# Pontos_Cegos_-_Rev_A.net
KiCad netlist of a schematic drawn in EAGLE
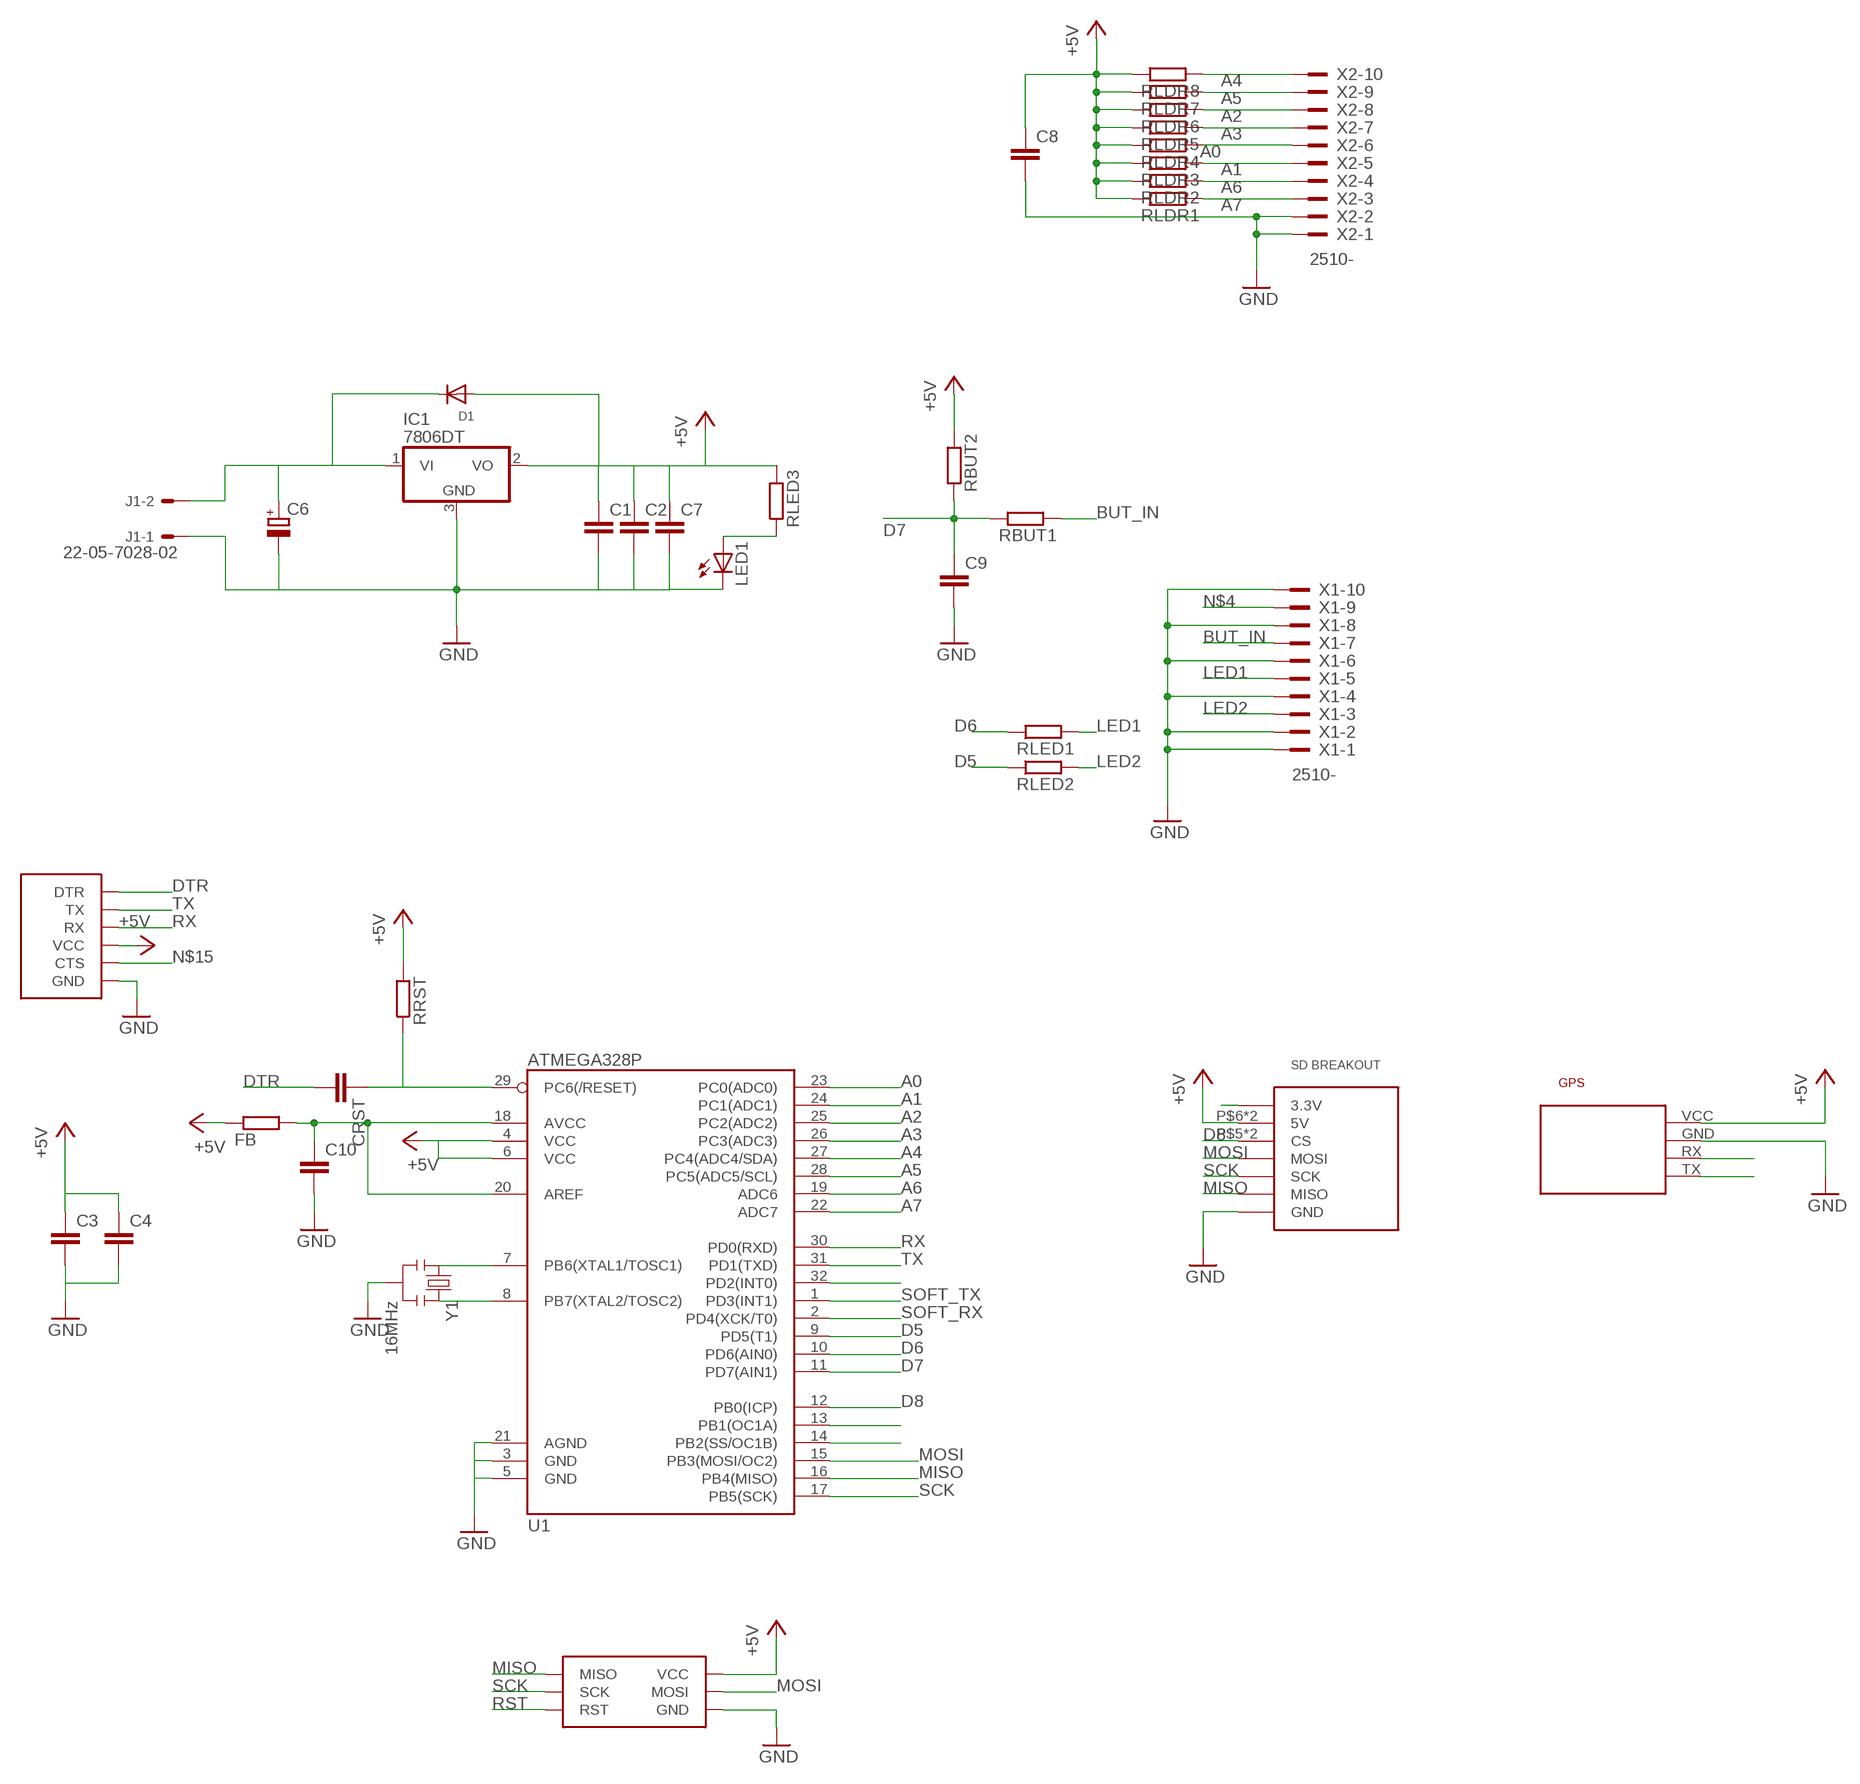
[diagram p0: schematic, sheet 1]

(export (version "E")
  (design (tool "Eeschema 10.0.6"))
  (components
    (comp (ref "C1")
      (value "C-EUC1210")
      (footprint "eagle-import:C1210")
      (libsource (lib "eagle-import") (part "C-EUC1210"))
    )
    (comp (ref "C2")
      (value "C-EUC1210")
      (footprint "eagle-import:C1210")
      (libsource (lib "eagle-import") (part "C-EUC1210"))
    )
    (comp (ref "C3")
      (value "C-EUC0603")
      (footprint "eagle-import:C0603")
      (libsource (lib "eagle-import") (part "C-EUC0603"))
    )
    (comp (ref "C4")
      (value "C-EUC0603")
      (footprint "eagle-import:C0603")
      (libsource (lib "eagle-import") (part "C-EUC0603"))
    )
    (comp (ref "C6")
      (value "CPOL-EUD")
      (footprint "eagle-import:PANASONIC_D")
      (libsource (lib "eagle-import") (part "CPOL-EUD"))
    )
    (comp (ref "C7")
      (value "C-EUC1210")
      (footprint "eagle-import:C1210")
      (libsource (lib "eagle-import") (part "C-EUC1210"))
    )
    (comp (ref "C8")
      (value "C-EUC0805")
      (footprint "eagle-import:C0805")
      (libsource (lib "eagle-import") (part "C-EUC0805"))
    )
    (comp (ref "C9")
      (value "C-EUC0805")
      (footprint "eagle-import:C0805")
      (libsource (lib "eagle-import") (part "C-EUC0805"))
    )
    (comp (ref "C10")
      (value "C-EUC0603")
      (footprint "eagle-import:C0603")
      (libsource (lib "eagle-import") (part "C-EUC0603"))
    )
    (comp (ref "CRST")
      (value "C-EUC0603")
      (footprint "eagle-import:C0603")
      (libsource (lib "eagle-import") (part "C-EUC0603"))
    )
    (comp (ref "D1")
      (value "DIODESMA")
      (footprint "eagle-import:SMADIODE")
      (libsource (lib "eagle-import") (part "DIODESMA"))
    )
    (comp (ref "FB")
      (value "R-EU_R0603")
      (footprint "eagle-import:R0603")
      (libsource (lib "eagle-import") (part "R-EU_R0603"))
    )
    (comp (ref "IC1")
      (value "7806DT")
      (footprint "eagle-import:TO252")
      (libsource (lib "eagle-import") (part "78DT06"))
    )
    (comp (ref "J1")
      (value "22-05-7028-02")
      (footprint "eagle-import:7395-02")
      (libsource (lib "eagle-import") (part "22-?-0205-7028"))
    )
    (comp (ref "LED1")
      (value "LED5MM")
      (footprint "eagle-import:LED5MM")
      (libsource (lib "eagle-import") (part "LED5MM"))
    )
    (comp (ref "RBUT1")
      (value "R-EU_R0603")
      (footprint "eagle-import:R0603")
      (libsource (lib "eagle-import") (part "R-EU_R0603"))
    )
    (comp (ref "RBUT2")
      (value "R-EU_R0603")
      (footprint "eagle-import:R0603")
      (libsource (lib "eagle-import") (part "R-EU_R0603"))
    )
    (comp (ref "RLDR1")
      (value "R-EU_R0603")
      (footprint "eagle-import:R0603")
      (libsource (lib "eagle-import") (part "R-EU_R0603"))
    )
    (comp (ref "RLDR2")
      (value "R-EU_R0603")
      (footprint "eagle-import:R0603")
      (libsource (lib "eagle-import") (part "R-EU_R0603"))
    )
    (comp (ref "RLDR3")
      (value "R-EU_R0603")
      (footprint "eagle-import:R0603")
      (libsource (lib "eagle-import") (part "R-EU_R0603"))
    )
    (comp (ref "RLDR4")
      (value "R-EU_R0603")
      (footprint "eagle-import:R0603")
      (libsource (lib "eagle-import") (part "R-EU_R0603"))
    )
    (comp (ref "RLDR5")
      (value "R-EU_R0603")
      (footprint "eagle-import:R0603")
      (libsource (lib "eagle-import") (part "R-EU_R0603"))
    )
    (comp (ref "RLDR6")
      (value "R-EU_R0603")
      (footprint "eagle-import:R0603")
      (libsource (lib "eagle-import") (part "R-EU_R0603"))
    )
    (comp (ref "RLDR7")
      (value "R-EU_R0603")
      (footprint "eagle-import:R0603")
      (libsource (lib "eagle-import") (part "R-EU_R0603"))
    )
    (comp (ref "RLDR8")
      (value "R-EU_R0603")
      (footprint "eagle-import:R0603")
      (libsource (lib "eagle-import") (part "R-EU_R0603"))
    )
    (comp (ref "RLED1")
      (value "R-EU_R0603")
      (footprint "eagle-import:R0603")
      (libsource (lib "eagle-import") (part "R-EU_R0603"))
    )
    (comp (ref "RLED2")
      (value "R-EU_R0603")
      (footprint "eagle-import:R0603")
      (libsource (lib "eagle-import") (part "R-EU_R0603"))
    )
    (comp (ref "RLED3")
      (value "R-EU_R0603")
      (footprint "eagle-import:R0603")
      (libsource (lib "eagle-import") (part "R-EU_R0603"))
    )
    (comp (ref "RRST")
      (value "R-EU_R0603")
      (footprint "eagle-import:R0603")
      (libsource (lib "eagle-import") (part "R-EU_R0603"))
    )
    (comp (ref "U$1")
      (value "ISP_POGOISP_POGO")
      (footprint "eagle-import:ISP_POGO")
      (libsource (lib "eagle-import") (part "ISP_POGOISP_POGO"))
    )
    (comp (ref "U$2")
      (value "SD_BREAKOUT")
      (footprint "eagle-import:SD_BREAKOUT")
      (libsource (lib "eagle-import") (part "SD_BREAKOUT"))
    )
    (comp (ref "U$3")
      (value "NEO6M_BREAKOUT")
      (footprint "eagle-import:NEO6M_BREAKOUT")
      (libsource (lib "eagle-import") (part "NEO6M_BREAKOUT"))
    )
    (comp (ref "U$4")
      (value "FTDI_HEADERSMD")
      (footprint "eagle-import:FTDI_HEADER_SMD")
      (libsource (lib "eagle-import") (part "FTDI_HEADERSMD"))
    )
    (comp (ref "U1")
      (value "ATMEGA328P")
      (footprint "eagle-import:TQFP32-08")
      (libsource (lib "eagle-import") (part "ATMEGA328_SMT"))
    )
    (comp (ref "X1")
      (value "2510-")
      (footprint "eagle-import:PAK100_2500-10")
      (fields (field (name "MF") "3M") (field (name "MPN") "2510-6002UB"))
      (libsource (lib "eagle-import") (part "2510-"))
    )
    (comp (ref "X2")
      (value "2510-")
      (footprint "eagle-import:PAK100_2500-10")
      (fields (field (name "MF") "3M") (field (name "MPN") "2510-6002UB"))
      (libsource (lib "eagle-import") (part "2510-"))
    )
    (comp (ref "Y1")
      (value "16MHz")
      (footprint "eagle-import:RESONATOR-SMD")
      (libsource (lib "eagle-import") (part "RESONATOR16MHZ"))
    )
  )
  (nets
    (net (code "1") (name "+5V") (class "Default")
      (node (ref "C1") (pin "1") (pinfunction "1_1") (pintype "passive"))
      (node (ref "C2") (pin "1") (pinfunction "1_1") (pintype "passive"))
      (node (ref "C3") (pin "1") (pinfunction "1_1") (pintype "passive"))
      (node (ref "C4") (pin "1") (pinfunction "1_1") (pintype "passive"))
      (node (ref "C7") (pin "1") (pinfunction "1_1") (pintype "passive"))
      (node (ref "C8") (pin "1") (pinfunction "1_1") (pintype "passive"))
      (node (ref "D1") (pin "A") (pinfunction "A_A") (pintype "passive"))
      (node (ref "FB") (pin "1") (pinfunction "1_1") (pintype "passive"))
      (node (ref "IC1") (pin "2") (pinfunction "VO_2") (pintype "passive"))
      (node (ref "RBUT2") (pin "2") (pinfunction "2_2") (pintype "passive"))
      (node (ref "RLDR1") (pin "1") (pinfunction "1_1") (pintype "passive"))
      (node (ref "RLDR2") (pin "1") (pinfunction "1_1") (pintype "passive"))
      (node (ref "RLDR3") (pin "1") (pinfunction "1_1") (pintype "passive"))
      (node (ref "RLDR4") (pin "1") (pinfunction "1_1") (pintype "passive"))
      (node (ref "RLDR5") (pin "1") (pinfunction "1_1") (pintype "passive"))
      (node (ref "RLDR6") (pin "1") (pinfunction "1_1") (pintype "passive"))
      (node (ref "RLDR7") (pin "1") (pinfunction "1_1") (pintype "passive"))
      (node (ref "RLDR8") (pin "1") (pinfunction "1_1") (pintype "passive"))
      (node (ref "RLED3") (pin "2") (pinfunction "2_2") (pintype "passive"))
      (node (ref "RRST") (pin "2") (pinfunction "2_2") (pintype "passive"))
      (node (ref "U$1") (pin "VCC") (pinfunction "VCC_VCC") (pintype "bidirectional"))
      (node (ref "U$2") (pin "P$14") (pinfunction "5V_P$14") (pintype "bidirectional"))
      (node (ref "U$2") (pin "P$6") (pinfunction "5V_P$6") (pintype "bidirectional"))
      (node (ref "U$3") (pin "VCC") (pinfunction "P$1_VCC") (pintype "bidirectional"))
      (node (ref "U$4") (pin "VCC") (pinfunction "VCC_VCC") (pintype "bidirectional"))
      (node (ref "U1") (pin "4") (pinfunction "VCC_4") (pintype "bidirectional"))
      (node (ref "U1") (pin "6") (pinfunction "VCC_6") (pintype "bidirectional"))
    )
    (net (code "2") (name "/A0") (class "Default")
      (node (ref "RLDR4") (pin "2") (pinfunction "2_2") (pintype "passive"))
      (node (ref "U1") (pin "23") (pinfunction "PC0(ADC0)_23") (pintype "bidirectional"))
      (node (ref "X2") (pin "6") (pinfunction "KL_6") (pintype "passive"))
    )
    (net (code "3") (name "/A1") (class "Default")
      (node (ref "RLDR3") (pin "2") (pinfunction "2_2") (pintype "passive"))
      (node (ref "U1") (pin "24") (pinfunction "PC1(ADC1)_24") (pintype "bidirectional"))
      (node (ref "X2") (pin "5") (pinfunction "KL_5") (pintype "passive"))
    )
    (net (code "4") (name "/A2") (class "Default")
      (node (ref "RLDR6") (pin "2") (pinfunction "2_2") (pintype "passive"))
      (node (ref "U1") (pin "25") (pinfunction "PC2(ADC2)_25") (pintype "bidirectional"))
      (node (ref "X2") (pin "8") (pinfunction "KL_8") (pintype "passive"))
    )
    (net (code "5") (name "/A3") (class "Default")
      (node (ref "RLDR5") (pin "2") (pinfunction "2_2") (pintype "passive"))
      (node (ref "U1") (pin "26") (pinfunction "PC3(ADC3)_26") (pintype "bidirectional"))
      (node (ref "X2") (pin "7") (pinfunction "KL_7") (pintype "passive"))
    )
    (net (code "6") (name "/A4") (class "Default")
      (node (ref "RLDR8") (pin "2") (pinfunction "2_2") (pintype "passive"))
      (node (ref "U1") (pin "27") (pinfunction "PC4(ADC4/SDA)_27") (pintype "bidirectional"))
      (node (ref "X2") (pin "10") (pinfunction "KL_10") (pintype "passive"))
    )
    (net (code "7") (name "/A5") (class "Default")
      (node (ref "RLDR7") (pin "2") (pinfunction "2_2") (pintype "passive"))
      (node (ref "U1") (pin "28") (pinfunction "PC5(ADC5/SCL)_28") (pintype "bidirectional"))
      (node (ref "X2") (pin "9") (pinfunction "KL_9") (pintype "passive"))
    )
    (net (code "8") (name "/A6") (class "Default")
      (node (ref "RLDR2") (pin "2") (pinfunction "2_2") (pintype "passive"))
      (node (ref "U1") (pin "19") (pinfunction "ADC6_19") (pintype "bidirectional"))
      (node (ref "X2") (pin "4") (pinfunction "KL_4") (pintype "passive"))
    )
    (net (code "9") (name "/A7") (class "Default")
      (node (ref "RLDR1") (pin "2") (pinfunction "2_2") (pintype "passive"))
      (node (ref "U1") (pin "22") (pinfunction "ADC7_22") (pintype "bidirectional"))
      (node (ref "X2") (pin "3") (pinfunction "KL_3") (pintype "passive"))
    )
    (net (code "10") (name "/BUT_IN") (class "Default")
      (node (ref "RBUT1") (pin "2") (pinfunction "2_2") (pintype "passive"))
      (node (ref "X1") (pin "7") (pinfunction "KL_7") (pintype "passive"))
    )
    (net (code "11") (name "/D5") (class "Default")
      (node (ref "RLED2") (pin "1") (pinfunction "1_1") (pintype "passive"))
      (node (ref "U1") (pin "9") (pinfunction "PD5(T1)_9") (pintype "bidirectional"))
    )
    (net (code "12") (name "/D6") (class "Default")
      (node (ref "RLED1") (pin "1") (pinfunction "1_1") (pintype "passive"))
      (node (ref "U1") (pin "10") (pinfunction "PD6(AIN0)_10") (pintype "bidirectional"))
    )
    (net (code "13") (name "/D7") (class "Default")
      (node (ref "C9") (pin "1") (pinfunction "1_1") (pintype "passive"))
      (node (ref "RBUT1") (pin "1") (pinfunction "1_1") (pintype "passive"))
      (node (ref "RBUT2") (pin "1") (pinfunction "1_1") (pintype "passive"))
      (node (ref "U1") (pin "11") (pinfunction "PD7(AIN1)_11") (pintype "bidirectional"))
    )
    (net (code "14") (name "/D8") (class "Default")
      (node (ref "U$2") (pin "P$13") (pinfunction "CS_P$13") (pintype "bidirectional"))
      (node (ref "U$2") (pin "P$5") (pinfunction "CS_P$5") (pintype "bidirectional"))
      (node (ref "U1") (pin "12") (pinfunction "PB0(ICP)_12") (pintype "bidirectional"))
    )
    (net (code "15") (name "/DTR") (class "Default")
      (node (ref "CRST") (pin "2") (pinfunction "2_2") (pintype "passive"))
      (node (ref "U$4") (pin "DTR") (pinfunction "DTR_DTR") (pintype "bidirectional"))
    )
    (net (code "16") (name "/LED1") (class "Default")
      (node (ref "RLED1") (pin "2") (pinfunction "2_2") (pintype "passive"))
      (node (ref "X1") (pin "5") (pinfunction "KL_5") (pintype "passive"))
    )
    (net (code "17") (name "/LED2") (class "Default")
      (node (ref "RLED2") (pin "2") (pinfunction "2_2") (pintype "passive"))
      (node (ref "X1") (pin "3") (pinfunction "KL_3") (pintype "passive"))
    )
    (net (code "18") (name "/MISO") (class "Default")
      (node (ref "U$1") (pin "MISO") (pinfunction "MISO_MISO") (pintype "bidirectional"))
      (node (ref "U$2") (pin "P$10") (pinfunction "MISO_P$10") (pintype "bidirectional"))
      (node (ref "U$2") (pin "P$2") (pinfunction "MISO_P$2") (pintype "bidirectional"))
      (node (ref "U1") (pin "16") (pinfunction "PB4(MISO)_16") (pintype "bidirectional"))
    )
    (net (code "19") (name "/MOSI") (class "Default")
      (node (ref "U$1") (pin "MOSI") (pinfunction "MOSI_MOSI") (pintype "bidirectional"))
      (node (ref "U$2") (pin "P$12") (pinfunction "MOSI_P$12") (pintype "bidirectional"))
      (node (ref "U$2") (pin "P$4") (pinfunction "MOSI_P$4") (pintype "bidirectional"))
      (node (ref "U1") (pin "15") (pinfunction "PB3(MOSI/OC2)_15") (pintype "bidirectional"))
    )
    (net (code "20") (name "/N$4") (class "Default")
      (node (ref "X1") (pin "9") (pinfunction "KL_9") (pintype "passive"))
    )
    (net (code "21") (name "/N$15") (class "Default")
      (node (ref "U$4") (pin "CTS") (pinfunction "CTS_CTS") (pintype "bidirectional"))
    )
    (net (code "22") (name "/RST") (class "Default")
      (node (ref "CRST") (pin "1") (pinfunction "1_1") (pintype "passive"))
      (node (ref "RRST") (pin "1") (pinfunction "1_1") (pintype "passive"))
      (node (ref "U$1") (pin "RST") (pinfunction "RST_RST") (pintype "bidirectional"))
      (node (ref "U1") (pin "29") (pinfunction "PC6(/RESET)_29") (pintype "bidirectional"))
    )
    (net (code "23") (name "/RX") (class "Default")
      (node (ref "U$4") (pin "RX") (pinfunction "RX_RX") (pintype "bidirectional"))
      (node (ref "U1") (pin "30") (pinfunction "PD0(RXD)_30") (pintype "bidirectional"))
    )
    (net (code "24") (name "/SCK") (class "Default")
      (node (ref "U$1") (pin "SCK") (pinfunction "SCK_SCK") (pintype "bidirectional"))
      (node (ref "U$2") (pin "P$11") (pinfunction "SCK_P$11") (pintype "bidirectional"))
      (node (ref "U$2") (pin "P$3") (pinfunction "SCK_P$3") (pintype "bidirectional"))
      (node (ref "U1") (pin "17") (pinfunction "PB5(SCK)_17") (pintype "bidirectional"))
    )
    (net (code "25") (name "/SOFT_RX") (class "Default")
      (node (ref "U$3") (pin "TX") (pinfunction "P$4_TX") (pintype "bidirectional"))
      (node (ref "U1") (pin "2") (pinfunction "PD4(XCK/T0)_2") (pintype "bidirectional"))
    )
    (net (code "26") (name "/SOFT_TX") (class "Default")
      (node (ref "U$3") (pin "RX") (pinfunction "P$3_RX") (pintype "bidirectional"))
      (node (ref "U1") (pin "1") (pinfunction "PD3(INT1)_1") (pintype "bidirectional"))
    )
    (net (code "27") (name "/TX") (class "Default")
      (node (ref "U$4") (pin "TX") (pinfunction "TX_TX") (pintype "bidirectional"))
      (node (ref "U1") (pin "31") (pinfunction "PD1(TXD)_31") (pintype "bidirectional"))
    )
    (net (code "28") (name "GND") (class "Default")
      (node (ref "C1") (pin "2") (pinfunction "2_2") (pintype "passive"))
      (node (ref "C10") (pin "2") (pinfunction "2_2") (pintype "passive"))
      (node (ref "C2") (pin "2") (pinfunction "2_2") (pintype "passive"))
      (node (ref "C3") (pin "2") (pinfunction "2_2") (pintype "passive"))
      (node (ref "C4") (pin "2") (pinfunction "2_2") (pintype "passive"))
      (node (ref "C6") (pin "-") (pinfunction "-_-") (pintype "passive"))
      (node (ref "C7") (pin "2") (pinfunction "2_2") (pintype "passive"))
      (node (ref "C8") (pin "2") (pinfunction "2_2") (pintype "passive"))
      (node (ref "C9") (pin "2") (pinfunction "2_2") (pintype "passive"))
      (node (ref "IC1") (pin "3") (pinfunction "GND_3") (pintype "passive"))
      (node (ref "J1") (pin "1") (pinfunction "S_1") (pintype "passive"))
      (node (ref "LED1") (pin "K") (pinfunction "C_K") (pintype "passive"))
      (node (ref "U$1") (pin "GND") (pinfunction "GND_GND") (pintype "bidirectional"))
      (node (ref "U$2") (pin "P$1") (pinfunction "GND_P$1") (pintype "bidirectional"))
      (node (ref "U$2") (pin "P$16") (pinfunction "GND_P$16") (pintype "bidirectional"))
      (node (ref "U$2") (pin "P$8") (pinfunction "GND_P$8") (pintype "bidirectional"))
      (node (ref "U$2") (pin "P$9") (pinfunction "GND_P$9") (pintype "bidirectional"))
      (node (ref "U$3") (pin "GND") (pinfunction "P$2_GND") (pintype "bidirectional"))
      (node (ref "U$4") (pin "GND") (pinfunction "GND_GND") (pintype "bidirectional"))
      (node (ref "U1") (pin "21") (pinfunction "AGND_21") (pintype "bidirectional"))
      (node (ref "U1") (pin "3") (pinfunction "GND_3") (pintype "bidirectional"))
      (node (ref "U1") (pin "5") (pinfunction "GND_5") (pintype "bidirectional"))
      (node (ref "X1") (pin "1") (pinfunction "KL_1") (pintype "passive"))
      (node (ref "X1") (pin "10") (pinfunction "KL_10") (pintype "passive"))
      (node (ref "X1") (pin "2") (pinfunction "KL_2") (pintype "passive"))
      (node (ref "X1") (pin "4") (pinfunction "KL_4") (pintype "passive"))
      (node (ref "X1") (pin "6") (pinfunction "KL_6") (pintype "passive"))
      (node (ref "X1") (pin "8") (pinfunction "KL_8") (pintype "passive"))
      (node (ref "X2") (pin "1") (pinfunction "KL_1") (pintype "passive"))
      (node (ref "X2") (pin "2") (pinfunction "KL_2") (pintype "passive"))
      (node (ref "Y1") (pin "2") (pinfunction "2_2") (pintype "passive"))
    )
    (net (code "29") (name "Net-(IC1-VI)") (class "Default")
      (node (ref "C6") (pin "+") (pinfunction "+_+") (pintype "passive"))
      (node (ref "D1") (pin "C") (pinfunction "C_C") (pintype "passive"))
      (node (ref "IC1") (pin "1") (pinfunction "VI_1") (pintype "input"))
      (node (ref "J1") (pin "2") (pinfunction "S_2") (pintype "passive"))
    )
    (net (code "30") (name "Net-(LED1-PadA)") (class "Default")
      (node (ref "LED1") (pin "A") (pinfunction "A_A") (pintype "passive"))
      (node (ref "RLED3") (pin "1") (pinfunction "1_1") (pintype "passive"))
    )
    (net (code "31") (name "Net-(U$2-3.3V-PadP$15)") (class "Default")
      (node (ref "U$2") (pin "P$15") (pinfunction "3.3V_P$15") (pintype "bidirectional"))
      (node (ref "U$2") (pin "P$7") (pinfunction "3.3V_P$7") (pintype "bidirectional"))
    )
    (net (code "32") (name "Net-(U1-AREF)") (class "Default")
      (node (ref "C10") (pin "1") (pinfunction "1_1") (pintype "passive"))
      (node (ref "FB") (pin "2") (pinfunction "2_2") (pintype "passive"))
      (node (ref "U1") (pin "18") (pinfunction "AVCC_18") (pintype "bidirectional"))
      (node (ref "U1") (pin "20") (pinfunction "AREF_20") (pintype "bidirectional"))
    )
    (net (code "33") (name "Net-(U1-PB6(XTAL1{slash}TOSC1))") (class "Default")
      (node (ref "U1") (pin "7") (pinfunction "PB6(XTAL1/TOSC1)_7") (pintype "bidirectional"))
      (node (ref "Y1") (pin "1") (pinfunction "1_1") (pintype "passive"))
    )
    (net (code "34") (name "Net-(U1-PB7(XTAL2{slash}TOSC2))") (class "Default")
      (node (ref "U1") (pin "8") (pinfunction "PB7(XTAL2/TOSC2)_8") (pintype "bidirectional"))
      (node (ref "Y1") (pin "3") (pinfunction "3_3") (pintype "passive"))
    )
    (net (code "35") (name "unconnected-(U1-PB1(OC1A)-Pad13)") (class "Default")
      (node (ref "U1") (pin "13") (pinfunction "PB1(OC1A)_13") (pintype "bidirectional"))
    )
    (net (code "36") (name "unconnected-(U1-PB2(SS{slash}OC1B)-Pad14)") (class "Default")
      (node (ref "U1") (pin "14") (pinfunction "PB2(SS/OC1B)_14") (pintype "bidirectional"))
    )
    (net (code "37") (name "unconnected-(U1-PD2(INT0)-Pad32)") (class "Default")
      (node (ref "U1") (pin "32") (pinfunction "PD2(INT0)_32") (pintype "bidirectional"))
    )
  )
)
